# controller.net
KiCad netlist of a schematic drawn in Altium Designer
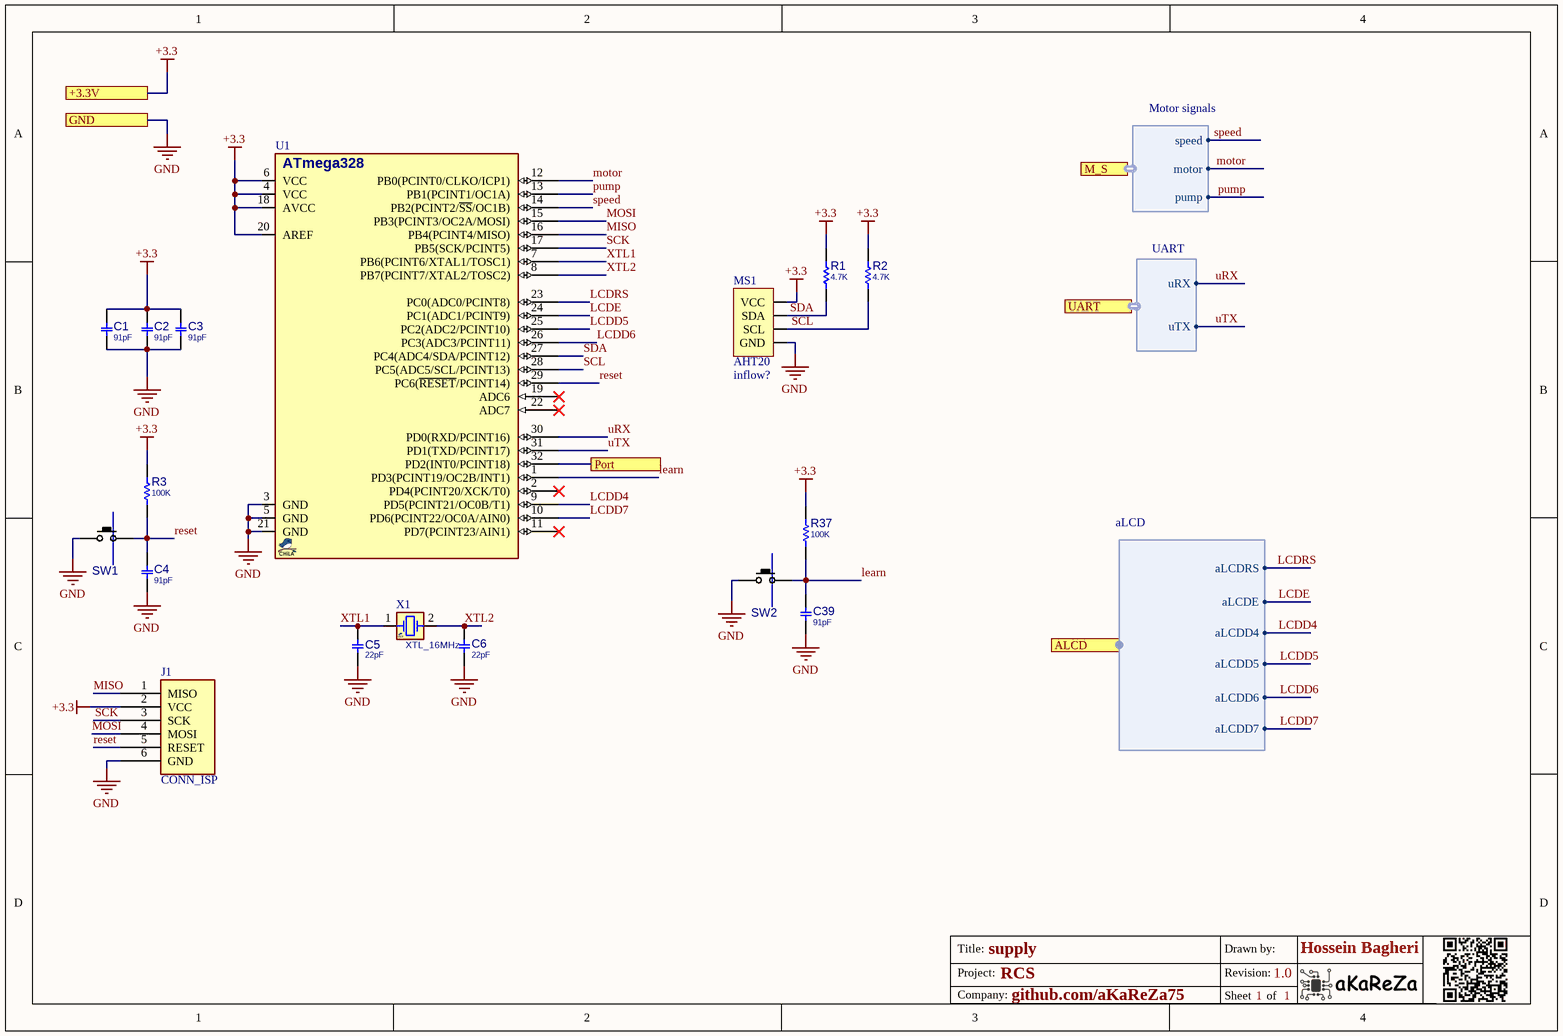
[diagram p0: controller.SchDoc]

(export (version "E")
  (design (tool "Eeschema 10.0.6"))
  (components
    (comp (ref "C1")
      (value "91pF")
      (footprint "C0805")
      (description "CAP, MLCC")
      (fields (field (name "MANF_P#") "UMK212ABJ225KG-T") (field (name "MANF") "Taiyo Yuden"))
      (libsource (lib "Chila_PCB") (part "CAP_SMD_MLCC_2.2u50V_0805"))
    )
    (comp (ref "C2")
      (value "91pF")
      (footprint "C0805")
      (description "CAP, MLCC")
      (fields (field (name "MANF_P#") "UMK212ABJ225KG-T") (field (name "MANF") "Taiyo Yuden"))
      (libsource (lib "Chila_PCB") (part "CAP_SMD_MLCC_2.2u50V_0805"))
    )
    (comp (ref "C3")
      (value "91pF")
      (footprint "C0805")
      (description "CAP, MLCC")
      (fields (field (name "MANF_P#") "UMK212ABJ225KG-T") (field (name "MANF") "Taiyo Yuden"))
      (libsource (lib "Chila_PCB") (part "CAP_SMD_MLCC_2.2u50V_0805"))
    )
    (comp (ref "C4")
      (value "91pF")
      (footprint "C0805")
      (description "CAP, MLCC")
      (fields (field (name "MANF_P#") "UMK212ABJ225KG-T") (field (name "MANF") "Taiyo Yuden"))
      (libsource (lib "Chila_PCB") (part "CAP_SMD_MLCC_2.2u50V_0805"))
    )
    (comp (ref "C5")
      (value "22pF")
      (footprint "C0805")
      (description "CAP, MLCC")
      (fields (field (name "MANF_P#") "UMK212ABJ225KG-T") (field (name "MANF") "Taiyo Yuden"))
      (libsource (lib "Chila_PCB") (part "CAP_SMD_MLCC_2.2u50V_0805"))
    )
    (comp (ref "C6")
      (value "22pF")
      (footprint "C0805")
      (description "CAP, MLCC")
      (fields (field (name "MANF_P#") "UMK212ABJ225KG-T") (field (name "MANF") "Taiyo Yuden"))
      (libsource (lib "Chila_PCB") (part "CAP_SMD_MLCC_2.2u50V_0805"))
    )
    (comp (ref "C39")
      (value "91pF")
      (footprint "C0805")
      (description "CAP, MLCC")
      (fields (field (name "MANF_P#") "UMK212ABJ225KG-T") (field (name "MANF") "Taiyo Yuden"))
      (libsource (lib "Chila_PCB") (part "CAP_SMD_MLCC_2.2u50V_0805"))
    )
    (comp (ref "J1")
      (value "CONN_ISP")
      (footprint "IDC_2X3")
      (description "CONN, ISP, AVR , HEADER BOX")
      (libsource (lib "Chila_PCB") (part "CONN_AVR_ISP_IDC6"))
    )
    (comp (ref "MS1")
      (value "AHT20")
      (footprint "AHT20")
      (description "Air Temperature and Humidity Sensor")
      (fields (field (name "INFLOW") "inflow?") (field (name "VALIDATION") "Valid"))
      (libsource (lib "aKaReZa") (part "ModSen_AHT20"))
    )
    (comp (ref "R1")
      (value "4.7K")
      (footprint "R0805")
      (description "RESISTOR, SMD")
      (libsource (lib "Chila_PCB") (part "RES_SMD_0805"))
    )
    (comp (ref "R2")
      (value "4.7K")
      (footprint "R0805")
      (description "RESISTOR, SMD")
      (libsource (lib "Chila_PCB") (part "RES_SMD_0805"))
    )
    (comp (ref "R3")
      (value "100K")
      (footprint "R0805")
      (description "RESISTOR, SMD")
      (libsource (lib "Chila_PCB") (part "RES_SMD_0805"))
    )
    (comp (ref "R37")
      (value "100K")
      (footprint "R0805")
      (description "RESISTOR, SMD")
      (libsource (lib "Chila_PCB") (part "RES_SMD_0805"))
    )
    (comp (ref "SW1")
      (value "PUSHBUTTON")
      (footprint "SWPBS_SPST_6X3X2")
      (description "SWITCH, PUSH BUTTON, TACTILE, SMD, SPST, 6X3.5X2.5mm")
      (fields (field (name "MANF") "C&K") (field (name "MANF_P#") "RS-282G05A3-SM RT"))
      (libsource (lib "Chila_PCB") (part "SWPBS_SPST_6X3X2_RS282"))
    )
    (comp (ref "SW2")
      (value "PUSHBUTTON")
      (footprint "SWPBS_SPST_6X3X2")
      (description "SWITCH, PUSH BUTTON, TACTILE, SMD, SPST, 6X3.5X2.5mm")
      (fields (field (name "MANF") "C&K") (field (name "MANF_P#") "RS-282G05A3-SM RT"))
      (libsource (lib "Chila_PCB") (part "SWPBS_SPST_6X3X2_RS282"))
    )
    (comp (ref "U1")
      (value "ATMEGA328")
      (footprint "QFG80_32")
      (description "MCU, AVR, 8-Bit, 16KB, 1KB RAM, 20MHz")
      (fields (field (name "MANF_P#") "ATMEGA328-AU") (field (name "MANF") "ATMEL/MICROCHIP"))
      (libsource (lib "Chila_PCB") (part "ATMEGA328_QFP32"))
    )
    (comp (ref "X1")
      (value "XTL_16MHz")
      (footprint "XTL_2_11X5")
      (description "Crystal MOST POPULAR ABL HC49 PACKAGE")
      (fields (field (name "MANF") "ABRACON") (field (name "MANF_P#") "ABLS-8.000MHZ-B4-T"))
      (libsource (lib "Chila_PCB") (part "XTL_2_HC49_8MHz_SMD"))
    )
  )
  (nets
    (net (code "5") (name "+3.3") (class "Default")
      (node (ref "C1") (pin "2") (pinfunction "2_2") (pintype "passive"))
      (node (ref "C2") (pin "2") (pinfunction "2_2") (pintype "passive"))
      (node (ref "C3") (pin "2") (pinfunction "2_2") (pintype "passive"))
      (node (ref "J1") (pin "2") (pinfunction "VCC_2") (pintype "passive"))
      (node (ref "MS1") (pin "4") (pinfunction "VCC_4") (pintype "passive"))
      (node (ref "R1") (pin "2") (pinfunction "2_2") (pintype "passive"))
      (node (ref "R2") (pin "2") (pinfunction "2_2") (pintype "passive"))
      (node (ref "R3") (pin "2") (pinfunction "2_2") (pintype "passive"))
      (node (ref "R37") (pin "2") (pinfunction "2_2") (pintype "passive"))
      (node (ref "U1") (pin "18") (pinfunction "AVCC_18") (pintype "power_in"))
      (node (ref "U1") (pin "20") (pinfunction "AREF_20") (pintype "passive"))
      (node (ref "U1") (pin "4") (pinfunction "VCC_4") (pintype "power_in"))
      (node (ref "U1") (pin "6") (pinfunction "VCC_6") (pintype "power_in"))
    )
    (net (code "6") (name "/LCDD4") (class "Default")
      (node (ref "U1") (pin "9") (pinfunction "PD5(PCINT21/OC0B/T1)_9") (pintype "bidirectional"))
    )
    (net (code "7") (name "/LCDD5") (class "Default")
      (node (ref "U1") (pin "25") (pinfunction "PC2(ADC2/PCINT10)_25") (pintype "bidirectional"))
    )
    (net (code "8") (name "/LCDD6") (class "Default")
      (node (ref "U1") (pin "26") (pinfunction "PC3(ADC3/PCINT11)_26") (pintype "bidirectional"))
    )
    (net (code "9") (name "/LCDD7") (class "Default")
      (node (ref "U1") (pin "10") (pinfunction "PD6(PCINT22/OC0A/AIN0)_10") (pintype "bidirectional"))
    )
    (net (code "10") (name "/LCDE") (class "Default")
      (node (ref "U1") (pin "24") (pinfunction "PC1(ADC1/PCINT9)_24") (pintype "bidirectional"))
    )
    (net (code "11") (name "/LCDRS") (class "Default")
      (node (ref "U1") (pin "23") (pinfunction "PC0(ADC0/PCINT8)_23") (pintype "bidirectional"))
    )
    (net (code "12") (name "/MISO") (class "Default")
      (node (ref "J1") (pin "1") (pinfunction "MISO_1") (pintype "passive"))
      (node (ref "U1") (pin "16") (pinfunction "PB4(PCINT4/MISO)_16") (pintype "bidirectional"))
    )
    (net (code "13") (name "/MOSI") (class "Default")
      (node (ref "J1") (pin "4") (pinfunction "MOSI_4") (pintype "passive"))
      (node (ref "U1") (pin "15") (pinfunction "PB3(PCINT3/OC2A/MOSI)_15") (pintype "bidirectional"))
    )
    (net (code "14") (name "/Port") (class "Default")
      (node (ref "U1") (pin "32") (pinfunction "PD2(INT0/PCINT18)_32") (pintype "bidirectional"))
    )
    (net (code "15") (name "/SCK") (class "Default")
      (node (ref "J1") (pin "3") (pinfunction "SCK_3") (pintype "passive"))
      (node (ref "U1") (pin "17") (pinfunction "PB5(SCK/PCINT5)_17") (pintype "bidirectional"))
    )
    (net (code "16") (name "/SCL") (class "Default")
      (node (ref "MS1") (pin "2") (pinfunction "SCL_2") (pintype "passive"))
      (node (ref "R2") (pin "1") (pinfunction "1_1") (pintype "passive"))
      (node (ref "U1") (pin "28") (pinfunction "PC5(ADC5/SCL/PCINT13)_28") (pintype "bidirectional"))
    )
    (net (code "17") (name "/SDA") (class "Default")
      (node (ref "MS1") (pin "1") (pinfunction "SDA_1") (pintype "passive"))
      (node (ref "R1") (pin "1") (pinfunction "1_1") (pintype "passive"))
      (node (ref "U1") (pin "27") (pinfunction "PC4(ADC4/SDA/PCINT12)_27") (pintype "bidirectional"))
    )
    (net (code "18") (name "/XTL1") (class "Default")
      (node (ref "C5") (pin "2") (pinfunction "2_2") (pintype "passive"))
      (node (ref "U1") (pin "7") (pinfunction "PB6(PCINT6/XTAL1/TOSC1)_7") (pintype "bidirectional"))
      (node (ref "X1") (pin "1") (pinfunction "OSC1_1") (pintype "passive"))
    )
    (net (code "19") (name "/XTL2") (class "Default")
      (node (ref "C6") (pin "2") (pinfunction "2_2") (pintype "passive"))
      (node (ref "U1") (pin "8") (pinfunction "PB7(PCINT7/XTAL2/TOSC2)_8") (pintype "bidirectional"))
      (node (ref "X1") (pin "2") (pinfunction "OSC2_2") (pintype "passive"))
    )
    (net (code "20") (name "/learn") (class "Default")
      (node (ref "C39") (pin "2") (pinfunction "2_2") (pintype "passive"))
      (node (ref "R37") (pin "1") (pinfunction "1_1") (pintype "passive"))
      (node (ref "SW2") (pin "2") (pinfunction "P3_2") (pintype "passive"))
      (node (ref "U1") (pin "1") (pinfunction "PD3(PCINT19/OC2B/INT1)_1") (pintype "bidirectional"))
    )
    (net (code "21") (name "/motor") (class "Default")
      (node (ref "U1") (pin "12") (pinfunction "PB0(PCINT0/CLKO/ICP1)_12") (pintype "bidirectional"))
    )
    (net (code "22") (name "/pump") (class "Default")
      (node (ref "U1") (pin "13") (pinfunction "PB1(PCINT1/OC1A)_13") (pintype "bidirectional"))
    )
    (net (code "23") (name "/reset") (class "Default")
      (node (ref "C4") (pin "2") (pinfunction "2_2") (pintype "passive"))
      (node (ref "J1") (pin "5") (pinfunction "RESET_5") (pintype "passive"))
      (node (ref "R3") (pin "1") (pinfunction "1_1") (pintype "passive"))
      (node (ref "SW1") (pin "2") (pinfunction "P3_2") (pintype "passive"))
      (node (ref "U1") (pin "29") (pinfunction "PC6(~{RESET}/PCINT14)_29") (pintype "bidirectional"))
    )
    (net (code "24") (name "/speed") (class "Default")
      (node (ref "U1") (pin "14") (pinfunction "PB2(PCINT2/~{SS}/OC1B)_14") (pintype "bidirectional"))
    )
    (net (code "25") (name "/uRX") (class "Default")
      (node (ref "U1") (pin "30") (pinfunction "PD0(RXD/PCINT16)_30") (pintype "bidirectional"))
    )
    (net (code "26") (name "/uTX") (class "Default")
      (node (ref "U1") (pin "31") (pinfunction "PD1(TXD/PCINT17)_31") (pintype "bidirectional"))
    )
    (net (code "30") (name "GND") (class "Default")
      (node (ref "C1") (pin "1") (pinfunction "1_1") (pintype "passive"))
      (node (ref "C2") (pin "1") (pinfunction "1_1") (pintype "passive"))
      (node (ref "C3") (pin "1") (pinfunction "1_1") (pintype "passive"))
      (node (ref "C39") (pin "1") (pinfunction "1_1") (pintype "passive"))
      (node (ref "C4") (pin "1") (pinfunction "1_1") (pintype "passive"))
      (node (ref "C5") (pin "1") (pinfunction "1_1") (pintype "passive"))
      (node (ref "C6") (pin "1") (pinfunction "1_1") (pintype "passive"))
      (node (ref "J1") (pin "6") (pinfunction "GND_6") (pintype "passive"))
      (node (ref "MS1") (pin "3") (pinfunction "GND_3") (pintype "passive"))
      (node (ref "SW1") (pin "1") (pinfunction "P1_1") (pintype "passive"))
      (node (ref "SW2") (pin "1") (pinfunction "P1_1") (pintype "passive"))
      (node (ref "U1") (pin "21") (pinfunction "GND_21") (pintype "power_in"))
      (node (ref "U1") (pin "3") (pinfunction "GND_3") (pintype "power_in"))
      (node (ref "U1") (pin "5") (pinfunction "GND_5") (pintype "power_in"))
    )
    (net (code "31") (name "unconnected-(U1-ADC6-Pad19)") (class "Default")
      (node (ref "U1") (pin "19") (pinfunction "ADC6_19") (pintype "input+no_connect"))
    )
    (net (code "32") (name "unconnected-(U1-ADC7-Pad22)") (class "Default")
      (node (ref "U1") (pin "22") (pinfunction "ADC7_22") (pintype "input+no_connect"))
    )
    (net (code "33") (name "unconnected-(U1-PD4(PCINT20{slash}XCK{slash}T0)-Pad2)") (class "Default")
      (node (ref "U1") (pin "2") (pinfunction "PD4(PCINT20/XCK/T0)_2") (pintype "bidirectional+no_connect"))
    )
    (net (code "34") (name "unconnected-(U1-PD7(PCINT23{slash}AIN1)-Pad11)") (class "Default")
      (node (ref "U1") (pin "11") (pinfunction "PD7(PCINT23/AIN1)_11") (pintype "bidirectional+no_connect"))
    )
  )
)
